# BaiDoXe_RFID.net
KiCad netlist of a schematic drawn in Altium Designer
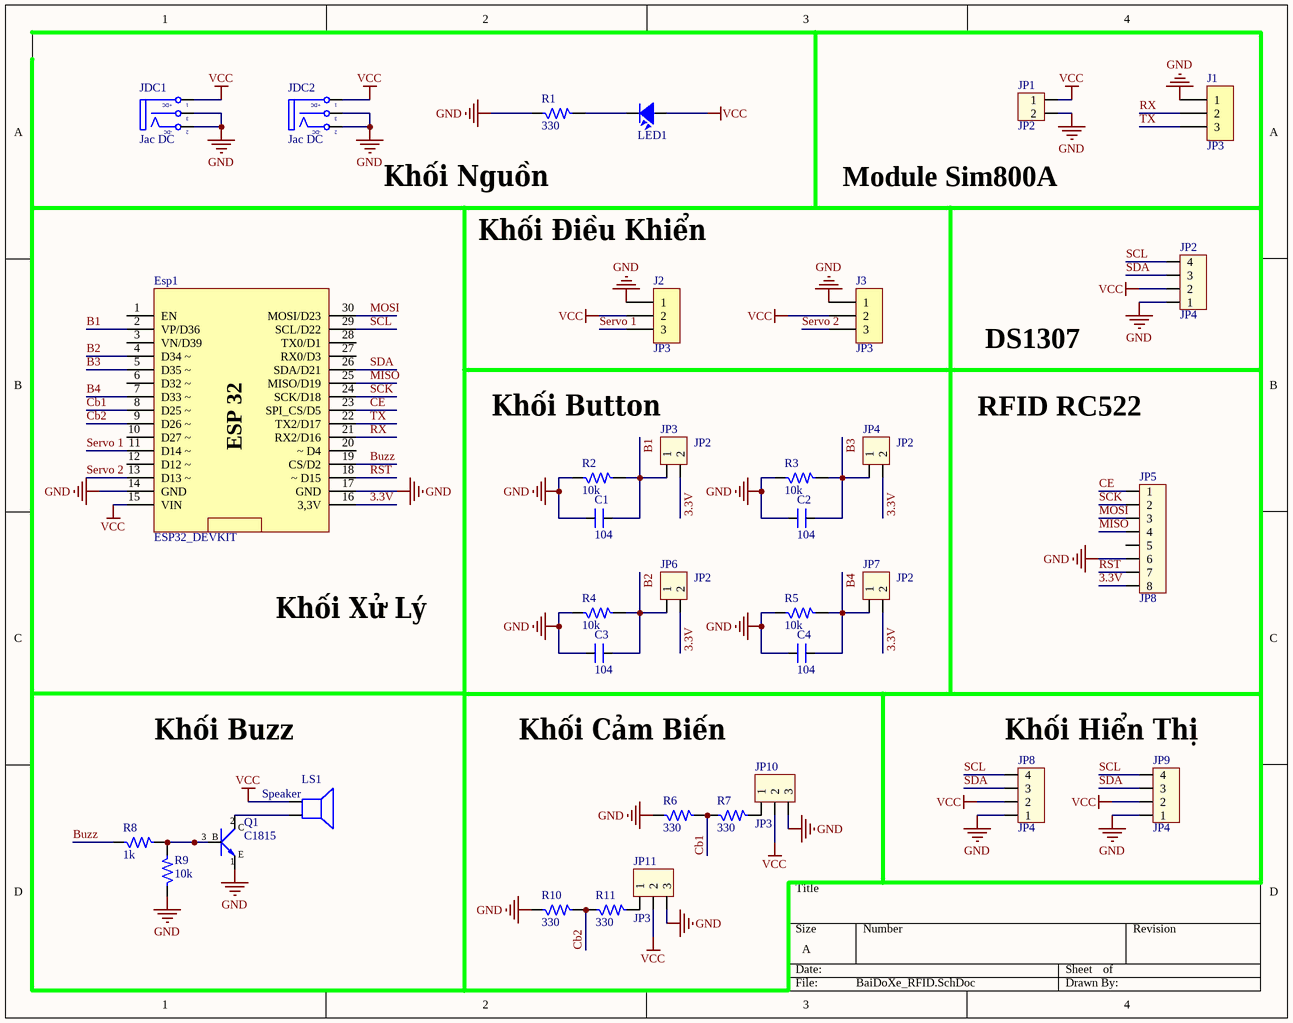
[diagram p0: BaiDoXe_RFID.SchDoc]

(export (version "E")
  (design (tool "Eeschema 10.0.6"))
  (components
    (comp (ref "C1")
      (value "104")
      (footprint "SM-CAP-0805")
      (fields (field (name "DESIGNED BY") "VanDungEvn"))
      (libsource (lib "syhaunguyen") (part "CN"))
    )
    (comp (ref "C2")
      (value "104")
      (footprint "SM-CAP-0805")
      (fields (field (name "DESIGNED BY") "VanDungEvn"))
      (libsource (lib "syhaunguyen") (part "CN"))
    )
    (comp (ref "C3")
      (value "104")
      (footprint "SM-CAP-0805")
      (fields (field (name "DESIGNED BY") "VanDungEvn"))
      (libsource (lib "syhaunguyen") (part "CN"))
    )
    (comp (ref "C4")
      (value "104")
      (footprint "SM-CAP-0805")
      (fields (field (name "DESIGNED BY") "VanDungEvn"))
      (libsource (lib "syhaunguyen") (part "CN"))
    )
    (comp (ref "Esp1")
      (value "ESP32_DEVKIT")
      (footprint "Esp32_Devkit")
      (libsource (lib "TDX_Local_LIbrary") (part "ESP32_DEVKIT"))
    )
    (comp (ref "J1")
      (value "JP3")
      (footprint "JUMP DON 3")
      (description "JUMP DON DUC 2.54")
      (libsource (lib "LinhKienDucLong") (part "JUMP 3"))
    )
    (comp (ref "J2")
      (value "JP3")
      (footprint "JUMP DON 3")
      (description "JUMP DON DUC 2.54")
      (libsource (lib "LinhKienDucLong") (part "JUMP 3"))
    )
    (comp (ref "J3")
      (value "JP3")
      (footprint "JUMP DON 3")
      (description "JUMP DON DUC 2.54")
      (libsource (lib "LinhKienDucLong") (part "JUMP 3"))
    )
    (comp (ref "JDC1")
      (value "Jac DC")
      (footprint "DC-IN")
      (description "Jac DC input")
      (libsource (lib "syhaunguyen") (part "DCIN"))
    )
    (comp (ref "JDC2")
      (value "Jac DC")
      (footprint "DC-IN")
      (description "Jac DC input")
      (libsource (lib "syhaunguyen") (part "DCIN"))
    )
    (comp (ref "JP1")
      (value "JP2")
      (footprint "CON2")
      (description "Connector 2")
      (libsource (lib "") (part "Con2_1"))
    )
    (comp (ref "JP2")
      (value "JP4")
      (footprint "CON4")
      (description "Connector 4")
      (libsource (lib "syhaunguyen") (part "Con4"))
    )
    (comp (ref "JP3")
      (value "JP2")
      (footprint "CON2")
      (description "Connector 2")
      (libsource (lib "syhaunguyen") (part "Con2"))
    )
    (comp (ref "JP4")
      (value "JP2")
      (footprint "CON2")
      (description "Connector 2")
      (libsource (lib "syhaunguyen") (part "Con2"))
    )
    (comp (ref "JP5")
      (value "JP8")
      (footprint "CON8")
      (description "Connector 8")
      (libsource (lib "syhaunguyen") (part "Con8"))
    )
    (comp (ref "JP6")
      (value "JP2")
      (footprint "CON2")
      (description "Connector 2")
      (libsource (lib "syhaunguyen") (part "Con2"))
    )
    (comp (ref "JP7")
      (value "JP2")
      (footprint "CON2")
      (description "Connector 2")
      (libsource (lib "syhaunguyen") (part "Con2"))
    )
    (comp (ref "JP8")
      (value "JP4")
      (footprint "CON4")
      (description "Connector 4")
      (libsource (lib "syhaunguyen") (part "Con4"))
    )
    (comp (ref "JP9")
      (value "JP4")
      (footprint "CON4")
      (description "Connector 4")
      (libsource (lib "syhaunguyen") (part "Con4"))
    )
    (comp (ref "JP10")
      (value "JP3")
      (footprint "CON3")
      (description "Connector 3")
      (libsource (lib "syhaunguyen") (part "Con3"))
    )
    (comp (ref "JP11")
      (value "JP3")
      (footprint "CON3")
      (description "Connector 3")
      (libsource (lib "syhaunguyen") (part "Con3"))
    )
    (comp (ref "LED1")
      (value "LED")
      (footprint "LED-5-BLUE")
      (description "LED Single colour Green and Red")
      (libsource (lib "syhaunguyen") (part "LED"))
    )
    (comp (ref "LS1")
      (value "Speaker")
      (footprint "SPEAKER")
      (description "Loudspeaker")
      (fields (field (name "PUBLISHER") "Altium Limited"))
      (libsource (lib "LIBRARY1") (part "Speaker"))
    )
    (comp (ref "Q1")
      (value "C1815")
      (footprint "SOT23B")
      (description "C1815 Dan (SMD)")
      (libsource (lib "LinhKienMCU.com") (part "C1815"))
    )
    (comp (ref "R1")
      (value "330")
      (footprint "res_0805")
      (description "TRO DAN 0805")
      (libsource (lib "LinhKienMCU.com") (part "RES 0805"))
    )
    (comp (ref "R2")
      (value "10k")
      (footprint "res_0805")
      (description "TRO DAN 0805")
      (libsource (lib "LinhKienMCU.com") (part "RES 0805"))
    )
    (comp (ref "R3")
      (value "10k")
      (footprint "res_0805")
      (description "TRO DAN 0805")
      (libsource (lib "LinhKienMCU.com") (part "RES 0805"))
    )
    (comp (ref "R4")
      (value "10k")
      (footprint "res_0805")
      (description "TRO DAN 0805")
      (libsource (lib "LinhKienMCU.com") (part "RES 0805"))
    )
    (comp (ref "R5")
      (value "10k")
      (footprint "res_0805")
      (description "TRO DAN 0805")
      (libsource (lib "LinhKienMCU.com") (part "RES 0805"))
    )
    (comp (ref "R6")
      (value "330")
      (footprint "res_0805")
      (description "TRO DAN 0805")
      (libsource (lib "LinhKienMCU.com") (part "RES 0805"))
    )
    (comp (ref "R7")
      (value "330")
      (footprint "res_0805")
      (description "TRO DAN 0805")
      (libsource (lib "LinhKienMCU.com") (part "RES 0805"))
    )
    (comp (ref "R8")
      (value "1k")
      (footprint "res_0805")
      (description "TRO DAN 0805")
      (libsource (lib "LinhKienMCU.com") (part "RES 0805"))
    )
    (comp (ref "R9")
      (value "10k")
      (footprint "res_0805")
      (description "TRO DAN 0805")
      (libsource (lib "LinhKienMCU.com") (part "RES 0805"))
    )
    (comp (ref "R10")
      (value "330")
      (footprint "res_0805")
      (description "TRO DAN 0805")
      (libsource (lib "LinhKienMCU.com") (part "RES 0805"))
    )
    (comp (ref "R11")
      (value "330")
      (footprint "res_0805")
      (description "TRO DAN 0805")
      (libsource (lib "LinhKienMCU.com") (part "RES 0805"))
    )
  )
  (nets
    (net (code "1") (name "/3.3V") (class "Default")
      (node (ref "Esp1") (pin "16") (pinfunction "3,3V_16") (pintype "passive"))
      (node (ref "JP3") (pin "2") (pinfunction "2_2") (pintype "passive"))
      (node (ref "JP4") (pin "2") (pinfunction "2_2") (pintype "passive"))
      (node (ref "JP5") (pin "8") (pinfunction "8_8") (pintype "passive"))
      (node (ref "JP6") (pin "2") (pinfunction "2_2") (pintype "passive"))
      (node (ref "JP7") (pin "2") (pinfunction "2_2") (pintype "passive"))
    )
    (net (code "2") (name "/B1") (class "Default")
      (node (ref "C1") (pin "2") (pinfunction "2_2") (pintype "passive"))
      (node (ref "Esp1") (pin "2") (pinfunction "VP/D36_2") (pintype "passive"))
      (node (ref "JP3") (pin "1") (pinfunction "1_1") (pintype "passive"))
      (node (ref "R2") (pin "2") (pinfunction "2_2") (pintype "passive"))
    )
    (net (code "3") (name "/B2") (class "Default")
      (node (ref "C3") (pin "2") (pinfunction "2_2") (pintype "passive"))
      (node (ref "Esp1") (pin "4") (pinfunction "D34_~_4") (pintype "passive"))
      (node (ref "JP6") (pin "1") (pinfunction "1_1") (pintype "passive"))
      (node (ref "R4") (pin "2") (pinfunction "2_2") (pintype "passive"))
    )
    (net (code "4") (name "/B3") (class "Default")
      (node (ref "C2") (pin "2") (pinfunction "2_2") (pintype "passive"))
      (node (ref "Esp1") (pin "5") (pinfunction "D35_~_5") (pintype "passive"))
      (node (ref "JP4") (pin "1") (pinfunction "1_1") (pintype "passive"))
      (node (ref "R3") (pin "2") (pinfunction "2_2") (pintype "passive"))
    )
    (net (code "5") (name "/B4") (class "Default")
      (node (ref "C4") (pin "2") (pinfunction "2_2") (pintype "passive"))
      (node (ref "Esp1") (pin "7") (pinfunction "D33_~_7") (pintype "passive"))
      (node (ref "JP7") (pin "1") (pinfunction "1_1") (pintype "passive"))
      (node (ref "R5") (pin "2") (pinfunction "2_2") (pintype "passive"))
    )
    (net (code "6") (name "/Buzz") (class "Default")
      (node (ref "Esp1") (pin "19") (pinfunction "CS/D2_19") (pintype "passive"))
      (node (ref "R8") (pin "1") (pinfunction "1_1") (pintype "passive"))
    )
    (net (code "7") (name "/CE") (class "Default")
      (node (ref "Esp1") (pin "23") (pinfunction "SPI_CS/D5_23") (pintype "passive"))
      (node (ref "JP5") (pin "1") (pinfunction "1_1") (pintype "passive"))
    )
    (net (code "8") (name "/Cb1") (class "Default")
      (node (ref "Esp1") (pin "8") (pinfunction "D25_~_8") (pintype "passive"))
      (node (ref "R6") (pin "2") (pinfunction "2_2") (pintype "passive"))
      (node (ref "R7") (pin "1") (pinfunction "1_1") (pintype "passive"))
    )
    (net (code "9") (name "/Cb2") (class "Default")
      (node (ref "Esp1") (pin "9") (pinfunction "D26_~_9") (pintype "passive"))
      (node (ref "R10") (pin "2") (pinfunction "2_2") (pintype "passive"))
      (node (ref "R11") (pin "1") (pinfunction "1_1") (pintype "passive"))
    )
    (net (code "10") (name "/MISO") (class "Default")
      (node (ref "Esp1") (pin "25") (pinfunction "MISO/D19_25") (pintype "passive"))
      (node (ref "JP5") (pin "4") (pinfunction "4_4") (pintype "passive"))
    )
    (net (code "11") (name "/MOSI") (class "Default")
      (node (ref "Esp1") (pin "30") (pinfunction "MOSI/D23_30") (pintype "passive"))
      (node (ref "JP5") (pin "3") (pinfunction "3_3") (pintype "passive"))
    )
    (net (code "12") (name "/RST") (class "Default")
      (node (ref "Esp1") (pin "18") (pinfunction "~_D15_18") (pintype "passive"))
      (node (ref "JP5") (pin "7") (pinfunction "7_7") (pintype "passive"))
    )
    (net (code "13") (name "/RX") (class "Default")
      (node (ref "Esp1") (pin "21") (pinfunction "RX2/D16_21") (pintype "passive"))
      (node (ref "J1") (pin "2") (pinfunction "2_2") (pintype "passive"))
    )
    (net (code "14") (name "/SCK") (class "Default")
      (node (ref "Esp1") (pin "24") (pinfunction "SCK/D18_24") (pintype "passive"))
      (node (ref "JP5") (pin "2") (pinfunction "2_2") (pintype "passive"))
    )
    (net (code "15") (name "/SCL") (class "Default")
      (node (ref "Esp1") (pin "29") (pinfunction "SCL/D22_29") (pintype "passive"))
      (node (ref "JP2") (pin "4") (pinfunction "4_4") (pintype "passive"))
      (node (ref "JP8") (pin "4") (pinfunction "4_4") (pintype "passive"))
      (node (ref "JP9") (pin "4") (pinfunction "4_4") (pintype "passive"))
    )
    (net (code "16") (name "/SDA") (class "Default")
      (node (ref "Esp1") (pin "26") (pinfunction "SDA/D21_26") (pintype "passive"))
      (node (ref "JP2") (pin "3") (pinfunction "3_3") (pintype "passive"))
      (node (ref "JP8") (pin "3") (pinfunction "3_3") (pintype "passive"))
      (node (ref "JP9") (pin "3") (pinfunction "3_3") (pintype "passive"))
    )
    (net (code "17") (name "/Servo 1") (class "Default")
      (node (ref "Esp1") (pin "11") (pinfunction "D14_~_11") (pintype "passive"))
      (node (ref "J2") (pin "3") (pinfunction "3_3") (pintype "passive"))
    )
    (net (code "18") (name "/Servo 2") (class "Default")
      (node (ref "Esp1") (pin "13") (pinfunction "D13_~_13") (pintype "passive"))
      (node (ref "J3") (pin "3") (pinfunction "3_3") (pintype "passive"))
    )
    (net (code "19") (name "/TX") (class "Default")
      (node (ref "Esp1") (pin "22") (pinfunction "TX2/D17_22") (pintype "passive"))
      (node (ref "J1") (pin "3") (pinfunction "3_3") (pintype "passive"))
    )
    (net (code "20") (name "GND") (class "Default")
      (node (ref "C1") (pin "1") (pinfunction "1_1") (pintype "passive"))
      (node (ref "C2") (pin "1") (pinfunction "1_1") (pintype "passive"))
      (node (ref "C3") (pin "1") (pinfunction "1_1") (pintype "passive"))
      (node (ref "C4") (pin "1") (pinfunction "1_1") (pintype "passive"))
      (node (ref "Esp1") (pin "14") (pinfunction "GND_14") (pintype "passive"))
      (node (ref "Esp1") (pin "17") (pinfunction "GND_17") (pintype "passive"))
      (node (ref "J1") (pin "1") (pinfunction "1_1") (pintype "passive"))
      (node (ref "J2") (pin "1") (pinfunction "1_1") (pintype "passive"))
      (node (ref "J3") (pin "1") (pinfunction "1_1") (pintype "passive"))
      (node (ref "JDC1") (pin "2") (pinfunction "TN_2") (pintype "passive"))
      (node (ref "JDC1") (pin "3") (pinfunction "S_3") (pintype "power_in"))
      (node (ref "JDC2") (pin "2") (pinfunction "TN_2") (pintype "passive"))
      (node (ref "JDC2") (pin "3") (pinfunction "S_3") (pintype "power_in"))
      (node (ref "JP1") (pin "2") (pinfunction "2_2") (pintype "passive"))
      (node (ref "JP10") (pin "3") (pinfunction "3_3") (pintype "passive"))
      (node (ref "JP11") (pin "3") (pinfunction "3_3") (pintype "passive"))
      (node (ref "JP2") (pin "1") (pinfunction "1_1") (pintype "passive"))
      (node (ref "JP5") (pin "6") (pinfunction "6_6") (pintype "passive"))
      (node (ref "JP8") (pin "1") (pinfunction "1_1") (pintype "passive"))
      (node (ref "JP9") (pin "1") (pinfunction "1_1") (pintype "passive"))
      (node (ref "Q1") (pin "1") (pinfunction "E_1") (pintype "passive"))
      (node (ref "R1") (pin "1") (pinfunction "1_1") (pintype "passive"))
      (node (ref "R10") (pin "1") (pinfunction "1_1") (pintype "passive"))
      (node (ref "R2") (pin "1") (pinfunction "1_1") (pintype "passive"))
      (node (ref "R3") (pin "1") (pinfunction "1_1") (pintype "passive"))
      (node (ref "R4") (pin "1") (pinfunction "1_1") (pintype "passive"))
      (node (ref "R5") (pin "1") (pinfunction "1_1") (pintype "passive"))
      (node (ref "R6") (pin "1") (pinfunction "1_1") (pintype "passive"))
      (node (ref "R9") (pin "1") (pinfunction "1_1") (pintype "passive"))
    )
    (net (code "21") (name "Net-(JP10-Pad1)") (class "Default")
      (node (ref "JP10") (pin "1") (pinfunction "1_1") (pintype "passive"))
      (node (ref "R7") (pin "2") (pinfunction "2_2") (pintype "passive"))
    )
    (net (code "22") (name "Net-(JP11-Pad1)") (class "Default")
      (node (ref "JP11") (pin "1") (pinfunction "1_1") (pintype "passive"))
      (node (ref "R11") (pin "2") (pinfunction "2_2") (pintype "passive"))
    )
    (net (code "23") (name "Net-(LED1-Pad2)") (class "Default")
      (node (ref "LED1") (pin "2") (pinfunction "2_2") (pintype "passive"))
      (node (ref "R1") (pin "2") (pinfunction "2_2") (pintype "passive"))
    )
    (net (code "24") (name "Net-(Q1-B)") (class "Default")
      (node (ref "Q1") (pin "3") (pinfunction "B_3") (pintype "passive"))
      (node (ref "R8") (pin "2") (pinfunction "2_2") (pintype "passive"))
      (node (ref "R9") (pin "2") (pinfunction "2_2") (pintype "passive"))
    )
    (net (code "25") (name "Net-(Q1-C)") (class "Default")
      (node (ref "LS1") (pin "2") (pinfunction "2_2") (pintype "passive"))
      (node (ref "Q1") (pin "2") (pinfunction "C_2") (pintype "passive"))
    )
    (net (code "26") (name "VCC") (class "Default")
      (node (ref "Esp1") (pin "15") (pinfunction "VIN_15") (pintype "passive"))
      (node (ref "J2") (pin "2") (pinfunction "2_2") (pintype "passive"))
      (node (ref "J3") (pin "2") (pinfunction "2_2") (pintype "passive"))
      (node (ref "JDC1") (pin "1") (pinfunction "T_1") (pintype "passive"))
      (node (ref "JDC2") (pin "1") (pinfunction "T_1") (pintype "passive"))
      (node (ref "JP1") (pin "1") (pinfunction "1_1") (pintype "passive"))
      (node (ref "JP10") (pin "2") (pinfunction "2_2") (pintype "passive"))
      (node (ref "JP11") (pin "2") (pinfunction "2_2") (pintype "passive"))
      (node (ref "JP2") (pin "2") (pinfunction "2_2") (pintype "passive"))
      (node (ref "JP8") (pin "2") (pinfunction "2_2") (pintype "passive"))
      (node (ref "JP9") (pin "2") (pinfunction "2_2") (pintype "passive"))
      (node (ref "LED1") (pin "1") (pinfunction "1_1") (pintype "passive"))
      (node (ref "LS1") (pin "1") (pinfunction "1_1") (pintype "passive"))
    )
    (net (code "27") (name "unconnected-(Esp1-D12_~-Pad12)") (class "Default")
      (node (ref "Esp1") (pin "12") (pinfunction "D12_~_12") (pintype "passive"))
    )
    (net (code "28") (name "unconnected-(Esp1-D27_~-Pad10)") (class "Default")
      (node (ref "Esp1") (pin "10") (pinfunction "D27_~_10") (pintype "passive"))
    )
    (net (code "29") (name "unconnected-(Esp1-D32_~-Pad6)") (class "Default")
      (node (ref "Esp1") (pin "6") (pinfunction "D32_~_6") (pintype "passive"))
    )
    (net (code "30") (name "unconnected-(Esp1-EN-Pad1)") (class "Default")
      (node (ref "Esp1") (pin "1") (pinfunction "EN_1") (pintype "passive"))
    )
    (net (code "31") (name "unconnected-(Esp1-RX0{slash}D3-Pad27)") (class "Default")
      (node (ref "Esp1") (pin "27") (pinfunction "RX0/D3_27") (pintype "passive"))
    )
    (net (code "32") (name "unconnected-(Esp1-TX0{slash}D1-Pad28)") (class "Default")
      (node (ref "Esp1") (pin "28") (pinfunction "TX0/D1_28") (pintype "passive"))
    )
    (net (code "33") (name "unconnected-(Esp1-VN{slash}D39-Pad3)") (class "Default")
      (node (ref "Esp1") (pin "3") (pinfunction "VN/D39_3") (pintype "passive"))
    )
    (net (code "34") (name "unconnected-(Esp1-~_D4-Pad20)") (class "Default")
      (node (ref "Esp1") (pin "20") (pinfunction "~_D4_20") (pintype "passive"))
    )
    (net (code "35") (name "unconnected-(JP5-Pad5)") (class "Default")
      (node (ref "JP5") (pin "5") (pinfunction "5_5") (pintype "passive"))
    )
  )
)
